# Schematic_Scout2Map_Altium.net
KiCad netlist of a schematic drawn in Altium Designer
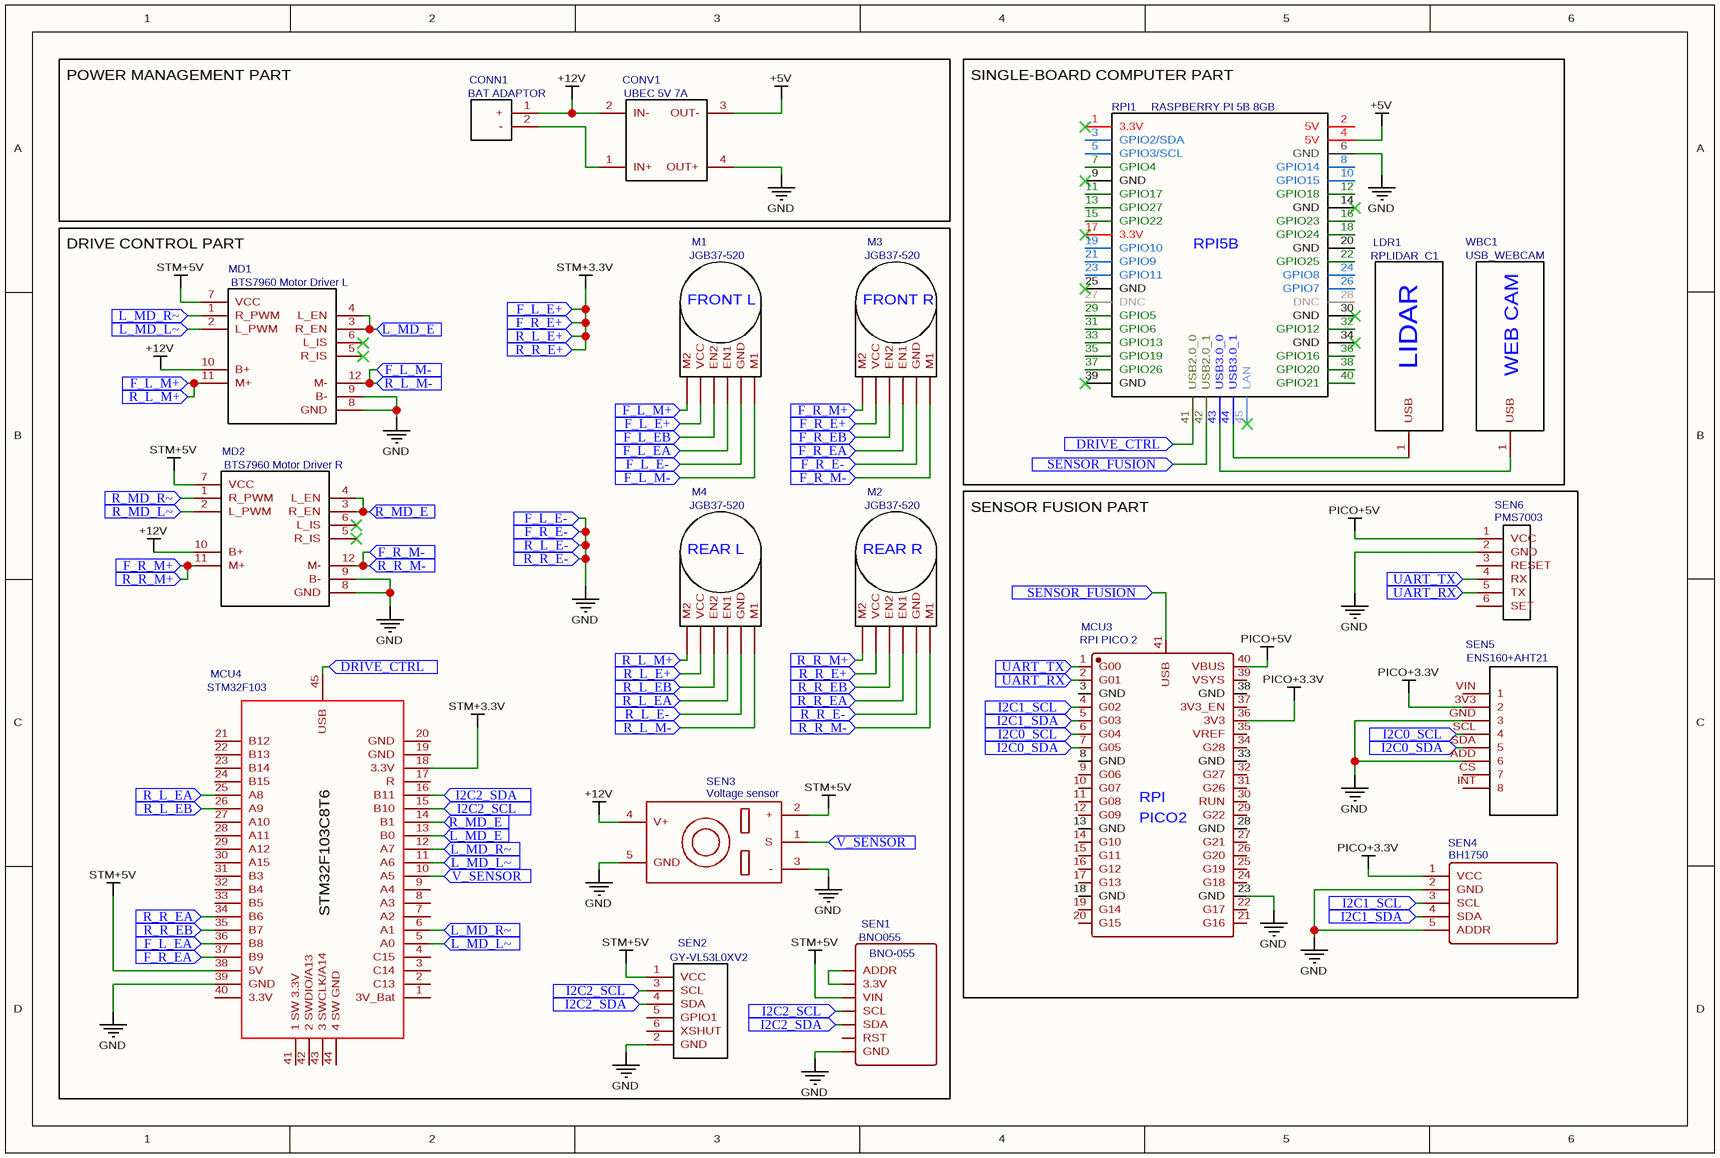
[diagram p0: Schematic_Scout2Map_Altium.schdoc]

(export (version "E")
  (design (tool "Eeschema 10.0.6"))
  (components
    (comp (ref "CONN1")
      (value "BAT ADAPTOR")
      (fields (field (name "CONTRIBUTOR") "odahmohammad361"))
      (libsource (lib "altium-import") (part "root_0_BAT ADAPTOR_"))
    )
    (comp (ref "CONV1")
      (value "UBEC 5V 7A")
      (fields (field (name "CONTRIBUTOR") "Nattanan"))
      (libsource (lib "altium-import") (part "root_1_UBEC 5V 7A_"))
    )
    (comp (ref "LDR1")
      (value "RPLIDAR_C1")
      (fields (field (name "CONTRIBUTOR") "jihoonkimtech (Jihoon Kim)"))
      (libsource (lib "altium-import") (part "root_1_RPLIDAR_C1_"))
    )
    (comp (ref "M1")
      (value "JGB37-520")
      (fields (field (name "CONTRIBUTOR") "preetpatel.svmr"))
      (libsource (lib "altium-import") (part "root_0_JGB37-520_"))
    )
    (comp (ref "M2")
      (value "JGB37-520")
      (fields (field (name "CONTRIBUTOR") "preetpatel.svmr"))
      (libsource (lib "altium-import") (part "root_0_JGB37-520_"))
    )
    (comp (ref "M3")
      (value "JGB37-520")
      (fields (field (name "CONTRIBUTOR") "preetpatel.svmr"))
      (libsource (lib "altium-import") (part "root_0_JGB37-520_"))
    )
    (comp (ref "M4")
      (value "JGB37-520")
      (fields (field (name "CONTRIBUTOR") "preetpatel.svmr"))
      (libsource (lib "altium-import") (part "root_0_JGB37-520_"))
    )
    (comp (ref "MCU3")
      (value "RPI PICO 2")
      (fields
        (field (name "MANUFACTURER") "Raspberry Pi")
        (field (name "MANUFACTURER PART") "SC0918")
        (field (name "CONTRIBUTOR") "jihoonkimtech (Jihoon Kim)")
      )
      (libsource (lib "altium-import") (part "root_0_RPI PICO 2_"))
    )
    (comp (ref "MCU4")
      (value "STM32F103")
      (fields
        (field (name "MANUFACTURER PART") "STM32F103C8T6")
        (field (name "CONTRIBUTOR") "jihoonkimtech (Jihoon Kim)")
      )
      (libsource (lib "altium-import") (part "root_0_STM32F103_"))
    )
    (comp (ref "MD1")
      (value "BTS7960 Motor Driver L")
      (fields (field (name "CONTRIBUTOR") "jihoonkimtech (Jihoon Kim)"))
      (libsource (lib "altium-import") (part "root_0_BTS7960 Motor Driver L_"))
    )
    (comp (ref "MD2")
      (value "BTS7960 Motor Driver R")
      (fields (field (name "CONTRIBUTOR") "jihoonkimtech (Jihoon Kim)"))
      (libsource (lib "altium-import") (part "root_0_BTS7960 Motor Driver R_"))
    )
    (comp (ref "RPI1")
      (value "RASPBERRY PI 5B 8GB")
      (fields
        (field (name "MANUFACTURER") "Raspberry Pi")
        (field (name "MANUFACTURER PART") "Raspberry Pi 4 Model B")
        (field (name "CONTRIBUTOR") "jihoonkimtech (Jihoon Kim)")
      )
      (libsource (lib "altium-import") (part "root_0_RASPBERRY PI 5B 8GB_"))
    )
    (comp (ref "SEN1")
      (value "BNO055")
      (fields (field (name "CONTRIBUTOR") "jihoonkim.tech"))
      (libsource (lib "altium-import") (part "root_0_BNO055_"))
    )
    (comp (ref "SEN2")
      (value "GY-VL53L0XV2")
      (fields (field (name "CONTRIBUTOR") "jihoonkimtech (Jihoon Kim)"))
      (libsource (lib "altium-import") (part "root_0_GY-VL53L0XV2_"))
    )
    (comp (ref "SEN3")
      (value "Voltage sensor")
      (fields (field (name "CONTRIBUTOR") "jihoonkimtech (Jihoon Kim)"))
      (libsource (lib "altium-import") (part "root_0_Voltage sensor_"))
    )
    (comp (ref "SEN4")
      (value "BH1750")
      (fields (field (name "CONTRIBUTOR") "vinhdoan"))
      (libsource (lib "altium-import") (part "root_3_BH1750_"))
    )
    (comp (ref "SEN5")
      (value "ENS160+AHT21")
      (fields (field (name "CONTRIBUTOR") "yoduc"))
      (libsource (lib "altium-import") (part "root_2_ENS160+AHT21_"))
    )
    (comp (ref "SEN6")
      (value "PMS7003")
      (fields (field (name "CONTRIBUTOR") "pb158"))
      (libsource (lib "altium-import") (part "root_0_PMS7003_"))
    )
    (comp (ref "WBC1")
      (value "USB_WEBCAM")
      (fields (field (name "CONTRIBUTOR") "jihoonkimtech (Jihoon Kim)"))
      (libsource (lib "altium-import") (part "root_1_USB_WEBCAM_"))
    )
  )
  (nets
    (net (code "1") (name "+5V") (class "Default")
      (node (ref "CONV1") (pin "3") (pinfunction "OUT-_3") (pintype "passive"))
      (node (ref "RPI1") (pin "4") (pinfunction "5V_4") (pintype "passive"))
    )
    (net (code "2") (name "+12V") (class "Default")
      (node (ref "CONN1") (pin "1") (pinfunction "+_1") (pintype "passive"))
      (node (ref "CONV1") (pin "2") (pinfunction "IN-_2") (pintype "passive"))
      (node (ref "MD1") (pin "10") (pinfunction "B+_10") (pintype "passive"))
      (node (ref "MD2") (pin "10") (pinfunction "B+_10") (pintype "passive"))
      (node (ref "SEN3") (pin "4") (pinfunction "V+_4") (pintype "passive"))
    )
    (net (code "3") (name "/DRIVE_CTRL") (class "Default")
      (node (ref "MCU4") (pin "45") (pinfunction "USB_45") (pintype "passive"))
      (node (ref "RPI1") (pin "41") (pinfunction "USB2.0_0_41") (pintype "passive"))
    )
    (net (code "4") (name "/F_L_EA") (class "Default")
      (node (ref "M1") (pin "3") (pinfunction "EN1_3") (pintype "passive"))
      (node (ref "MCU4") (pin "36") (pinfunction "B8_36") (pintype "passive"))
    )
    (net (code "5") (name "/F_L_EB") (class "Default")
      (node (ref "M1") (pin "4") (pinfunction "EN2_4") (pintype "passive"))
    )
    (net (code "6") (name "/F_L_M+") (class "Default")
      (node (ref "M1") (pin "6") (pinfunction "M2_6") (pintype "passive"))
      (node (ref "M4") (pin "6") (pinfunction "M2_6") (pintype "passive"))
      (node (ref "MD1") (pin "11") (pinfunction "M+_11") (pintype "passive"))
    )
    (net (code "7") (name "/F_L_M-") (class "Default")
      (node (ref "M1") (pin "1") (pinfunction "M1_1") (pintype "passive"))
      (node (ref "M4") (pin "1") (pinfunction "M1_1") (pintype "passive"))
      (node (ref "MD1") (pin "12") (pinfunction "M-_12") (pintype "passive"))
    )
    (net (code "8") (name "/F_R_EA") (class "Default")
      (node (ref "M3") (pin "3") (pinfunction "EN1_3") (pintype "passive"))
      (node (ref "MCU4") (pin "37") (pinfunction "B9_37") (pintype "passive"))
    )
    (net (code "9") (name "/F_R_EB") (class "Default")
      (node (ref "M3") (pin "4") (pinfunction "EN2_4") (pintype "passive"))
    )
    (net (code "10") (name "/F_R_M+") (class "Default")
      (node (ref "M2") (pin "6") (pinfunction "M2_6") (pintype "passive"))
      (node (ref "M3") (pin "6") (pinfunction "M2_6") (pintype "passive"))
      (node (ref "MD2") (pin "11") (pinfunction "M+_11") (pintype "passive"))
    )
    (net (code "11") (name "/F_R_M-") (class "Default")
      (node (ref "M2") (pin "1") (pinfunction "M1_1") (pintype "passive"))
      (node (ref "M3") (pin "1") (pinfunction "M1_1") (pintype "passive"))
      (node (ref "MD2") (pin "12") (pinfunction "M-_12") (pintype "passive"))
    )
    (net (code "12") (name "/I2C0_SCL") (class "Default")
      (node (ref "MCU3") (pin "6") (pinfunction "G04_6") (pintype "passive"))
      (node (ref "SEN5") (pin "SCL") (pinfunction "4_SCL") (pintype "passive"))
    )
    (net (code "13") (name "/I2C0_SDA") (class "Default")
      (node (ref "MCU3") (pin "7") (pinfunction "G05_7") (pintype "passive"))
      (node (ref "SEN5") (pin "SDA") (pinfunction "5_SDA") (pintype "passive"))
    )
    (net (code "14") (name "/I2C1_SCL") (class "Default")
      (node (ref "MCU3") (pin "4") (pinfunction "G02_4") (pintype "passive"))
      (node (ref "SEN4") (pin "3") (pinfunction "SCL_3") (pintype "passive"))
    )
    (net (code "15") (name "/I2C1_SDA") (class "Default")
      (node (ref "MCU3") (pin "5") (pinfunction "G03_5") (pintype "passive"))
      (node (ref "SEN4") (pin "4") (pinfunction "SDA_4") (pintype "passive"))
    )
    (net (code "16") (name "/I2C2_SCL") (class "Default")
      (node (ref "MCU4") (pin "15") (pinfunction "B10_15") (pintype "passive"))
      (node (ref "SEN1") (pin "4") (pinfunction "SCL_4") (pintype "passive"))
      (node (ref "SEN2") (pin "3") (pinfunction "SCL_3") (pintype "passive"))
    )
    (net (code "17") (name "/I2C2_SDA") (class "Default")
      (node (ref "MCU4") (pin "16") (pinfunction "B11_16") (pintype "passive"))
      (node (ref "SEN1") (pin "5") (pinfunction "SDA_5") (pintype "passive"))
      (node (ref "SEN2") (pin "4") (pinfunction "SDA_4") (pintype "passive"))
    )
    (net (code "18") (name "/L_MD_E") (class "Default")
      (node (ref "MCU4") (pin "13") (pinfunction "B0_13") (pintype "passive"))
      (node (ref "MD1") (pin "3") (pinfunction "R_EN_3") (pintype "passive"))
      (node (ref "MD1") (pin "4") (pinfunction "L_EN_4") (pintype "passive"))
    )
    (net (code "19") (name "/L_MD_L~") (class "Default")
      (node (ref "MCU4") (pin "11") (pinfunction "A6_11") (pintype "passive"))
      (node (ref "MCU4") (pin "5") (pinfunction "A0_5") (pintype "passive"))
      (node (ref "MD1") (pin "2") (pinfunction "L_PWM_2") (pintype "passive"))
    )
    (net (code "20") (name "/L_MD_R~") (class "Default")
      (node (ref "MCU4") (pin "12") (pinfunction "A7_12") (pintype "passive"))
      (node (ref "MCU4") (pin "6") (pinfunction "A1_6") (pintype "passive"))
      (node (ref "MD1") (pin "1") (pinfunction "R_PWM_1") (pintype "passive"))
    )
    (net (code "21") (name "/R_L_EA") (class "Default")
      (node (ref "M4") (pin "3") (pinfunction "EN1_3") (pintype "passive"))
      (node (ref "MCU4") (pin "25") (pinfunction "A8_25") (pintype "passive"))
    )
    (net (code "22") (name "/R_L_EB") (class "Default")
      (node (ref "M4") (pin "4") (pinfunction "EN2_4") (pintype "passive"))
      (node (ref "MCU4") (pin "26") (pinfunction "A9_26") (pintype "passive"))
    )
    (net (code "23") (name "/R_MD_E") (class "Default")
      (node (ref "MCU4") (pin "14") (pinfunction "B1_14") (pintype "passive"))
      (node (ref "MD2") (pin "3") (pinfunction "R_EN_3") (pintype "passive"))
      (node (ref "MD2") (pin "4") (pinfunction "L_EN_4") (pintype "passive"))
    )
    (net (code "24") (name "/R_MD_L~") (class "Default")
      (node (ref "MD2") (pin "2") (pinfunction "L_PWM_2") (pintype "passive"))
    )
    (net (code "25") (name "/R_MD_R~") (class "Default")
      (node (ref "MD2") (pin "1") (pinfunction "R_PWM_1") (pintype "passive"))
    )
    (net (code "26") (name "/R_R_EA") (class "Default")
      (node (ref "M2") (pin "3") (pinfunction "EN1_3") (pintype "passive"))
      (node (ref "MCU4") (pin "34") (pinfunction "B6_34") (pintype "passive"))
    )
    (net (code "27") (name "/R_R_EB") (class "Default")
      (node (ref "M2") (pin "4") (pinfunction "EN2_4") (pintype "passive"))
      (node (ref "MCU4") (pin "35") (pinfunction "B7_35") (pintype "passive"))
    )
    (net (code "28") (name "/SENSOR_FUSION") (class "Default")
      (node (ref "MCU3") (pin "41") (pinfunction "USB_41") (pintype "passive"))
      (node (ref "RPI1") (pin "42") (pinfunction "USB2.0_1_42") (pintype "passive"))
    )
    (net (code "29") (name "/UART_RX") (class "Default")
      (node (ref "MCU3") (pin "2") (pinfunction "G01_2") (pintype "passive"))
      (node (ref "SEN6") (pin "5") (pinfunction "TX_5") (pintype "passive"))
    )
    (net (code "30") (name "/UART_TX") (class "Default")
      (node (ref "MCU3") (pin "1") (pinfunction "G00_1") (pintype "passive"))
      (node (ref "SEN6") (pin "4") (pinfunction "RX_4") (pintype "passive"))
    )
    (net (code "31") (name "/V_SENSOR") (class "Default")
      (node (ref "MCU4") (pin "10") (pinfunction "A5_10") (pintype "passive"))
      (node (ref "SEN3") (pin "1") (pinfunction "S_1") (pintype "passive"))
    )
    (net (code "32") (name "GND") (class "Default")
      (node (ref "CONV1") (pin "4") (pinfunction "OUT+_4") (pintype "passive"))
      (node (ref "M1") (pin "2") (pinfunction "GND_2") (pintype "passive"))
      (node (ref "M2") (pin "2") (pinfunction "GND_2") (pintype "passive"))
      (node (ref "M3") (pin "2") (pinfunction "GND_2") (pintype "passive"))
      (node (ref "M4") (pin "2") (pinfunction "GND_2") (pintype "passive"))
      (node (ref "MCU3") (pin "23") (pinfunction "GND_23") (pintype "passive"))
      (node (ref "MCU4") (pin "39") (pinfunction "GND_39") (pintype "passive"))
      (node (ref "MD1") (pin "8") (pinfunction "GND_8") (pintype "passive"))
      (node (ref "MD1") (pin "9") (pinfunction "B-_9") (pintype "passive"))
      (node (ref "MD2") (pin "8") (pinfunction "GND_8") (pintype "passive"))
      (node (ref "MD2") (pin "9") (pinfunction "B-_9") (pintype "passive"))
      (node (ref "RPI1") (pin "6") (pinfunction "GND_6") (pintype "passive"))
      (node (ref "SEN1") (pin "3") (pinfunction "GND_3") (pintype "passive"))
      (node (ref "SEN2") (pin "2") (pinfunction "GND_2") (pintype "passive"))
      (node (ref "SEN3") (pin "3") (pinfunction "-_3") (pintype "passive"))
      (node (ref "SEN3") (pin "5") (pinfunction "GND_5") (pintype "passive"))
      (node (ref "SEN4") (pin "2") (pinfunction "GND_2") (pintype "passive"))
      (node (ref "SEN4") (pin "5") (pinfunction "ADDR_5") (pintype "passive"))
      (node (ref "SEN5") (pin "ADD") (pinfunction "6_ADD") (pintype "passive"))
      (node (ref "SEN5") (pin "GND") (pinfunction "3_GND") (pintype "passive"))
      (node (ref "SEN6") (pin "2") (pinfunction "GND_2") (pintype "passive"))
    )
    (net (code "33") (name "Net-(CONN1--)") (class "Default")
      (node (ref "CONN1") (pin "2") (pinfunction "-_2") (pintype "passive"))
      (node (ref "CONV1") (pin "1") (pinfunction "IN+_1") (pintype "passive"))
    )
    (net (code "34") (name "Net-(LDR1-USB)") (class "Default")
      (node (ref "LDR1") (pin "1") (pinfunction "USB_1") (pintype "passive"))
      (node (ref "RPI1") (pin "44") (pinfunction "USB3.0_1_44") (pintype "passive"))
    )
    (net (code "35") (name "Net-(RPI1-USB3.0_0)") (class "Default")
      (node (ref "RPI1") (pin "43") (pinfunction "USB3.0_0_43") (pintype "passive"))
      (node (ref "WBC1") (pin "1") (pinfunction "USB_1") (pintype "passive"))
    )
    (net (code "36") (name "Net-(SEN1-3.3V)") (class "Default")
      (node (ref "SEN1") (pin "2") (pinfunction "3.3V_2") (pintype "passive"))
      (node (ref "SEN1") (pin "6") (pinfunction "ADDR_6") (pintype "passive"))
    )
    (net (code "37") (name "PICO+3.3V") (class "Default")
      (node (ref "MCU3") (pin "36") (pinfunction "3V3_36") (pintype "passive"))
      (node (ref "SEN4") (pin "1") (pinfunction "VCC_1") (pintype "passive"))
      (node (ref "SEN5") (pin "3V3") (pinfunction "2_3V3") (pintype "passive"))
    )
    (net (code "38") (name "PICO+5V") (class "Default")
      (node (ref "MCU3") (pin "40") (pinfunction "VBUS_40") (pintype "passive"))
      (node (ref "SEN6") (pin "1") (pinfunction "VCC_1") (pintype "passive"))
    )
    (net (code "39") (name "STM+3.3V") (class "Default")
      (node (ref "M1") (pin "5") (pinfunction "VCC_5") (pintype "passive"))
      (node (ref "M2") (pin "5") (pinfunction "VCC_5") (pintype "passive"))
      (node (ref "M3") (pin "5") (pinfunction "VCC_5") (pintype "passive"))
      (node (ref "M4") (pin "5") (pinfunction "VCC_5") (pintype "passive"))
      (node (ref "MCU4") (pin "18") (pinfunction "3.3V_18") (pintype "passive"))
    )
    (net (code "40") (name "STM+5V") (class "Default")
      (node (ref "MCU4") (pin "38") (pinfunction "5V_38") (pintype "passive"))
      (node (ref "MD1") (pin "7") (pinfunction "VCC_7") (pintype "passive"))
      (node (ref "MD2") (pin "7") (pinfunction "VCC_7") (pintype "passive"))
      (node (ref "SEN1") (pin "1") (pinfunction "VIN_1") (pintype "passive"))
      (node (ref "SEN2") (pin "1") (pinfunction "VCC_1") (pintype "passive"))
      (node (ref "SEN3") (pin "2") (pinfunction "+_2") (pintype "passive"))
    )
    (net (code "41") (name "unconnected-(MCU3-3V3_EN-Pad37)") (class "Default")
      (node (ref "MCU3") (pin "37") (pinfunction "3V3_EN_37") (pintype "passive"))
    )
    (net (code "42") (name "unconnected-(MCU3-G06-Pad9)") (class "Default")
      (node (ref "MCU3") (pin "9") (pinfunction "G06_9") (pintype "passive"))
    )
    (net (code "43") (name "unconnected-(MCU3-G07-Pad10)") (class "Default")
      (node (ref "MCU3") (pin "10") (pinfunction "G07_10") (pintype "passive"))
    )
    (net (code "44") (name "unconnected-(MCU3-G08-Pad11)") (class "Default")
      (node (ref "MCU3") (pin "11") (pinfunction "G08_11") (pintype "passive"))
    )
    (net (code "45") (name "unconnected-(MCU3-G09-Pad12)") (class "Default")
      (node (ref "MCU3") (pin "12") (pinfunction "G09_12") (pintype "passive"))
    )
    (net (code "46") (name "unconnected-(MCU3-G10-Pad14)") (class "Default")
      (node (ref "MCU3") (pin "14") (pinfunction "G10_14") (pintype "passive"))
    )
    (net (code "47") (name "unconnected-(MCU3-G11-Pad15)") (class "Default")
      (node (ref "MCU3") (pin "15") (pinfunction "G11_15") (pintype "passive"))
    )
    (net (code "48") (name "unconnected-(MCU3-G12-Pad16)") (class "Default")
      (node (ref "MCU3") (pin "16") (pinfunction "G12_16") (pintype "passive"))
    )
    (net (code "49") (name "unconnected-(MCU3-G13-Pad17)") (class "Default")
      (node (ref "MCU3") (pin "17") (pinfunction "G13_17") (pintype "passive"))
    )
    (net (code "50") (name "unconnected-(MCU3-G14-Pad19)") (class "Default")
      (node (ref "MCU3") (pin "19") (pinfunction "G14_19") (pintype "passive"))
    )
    (net (code "51") (name "unconnected-(MCU3-G15-Pad20)") (class "Default")
      (node (ref "MCU3") (pin "20") (pinfunction "G15_20") (pintype "passive"))
    )
    (net (code "52") (name "unconnected-(MCU3-G16-Pad21)") (class "Default")
      (node (ref "MCU3") (pin "21") (pinfunction "G16_21") (pintype "passive"))
    )
    (net (code "53") (name "unconnected-(MCU3-G17-Pad22)") (class "Default")
      (node (ref "MCU3") (pin "22") (pinfunction "G17_22") (pintype "passive"))
    )
    (net (code "54") (name "unconnected-(MCU3-G18-Pad24)") (class "Default")
      (node (ref "MCU3") (pin "24") (pinfunction "G18_24") (pintype "passive"))
    )
    (net (code "55") (name "unconnected-(MCU3-G19-Pad25)") (class "Default")
      (node (ref "MCU3") (pin "25") (pinfunction "G19_25") (pintype "passive"))
    )
    (net (code "56") (name "unconnected-(MCU3-G20-Pad26)") (class "Default")
      (node (ref "MCU3") (pin "26") (pinfunction "G20_26") (pintype "passive"))
    )
    (net (code "57") (name "unconnected-(MCU3-G21-Pad27)") (class "Default")
      (node (ref "MCU3") (pin "27") (pinfunction "G21_27") (pintype "passive"))
    )
    (net (code "58") (name "unconnected-(MCU3-G22-Pad29)") (class "Default")
      (node (ref "MCU3") (pin "29") (pinfunction "G22_29") (pintype "passive"))
    )
    (net (code "59") (name "unconnected-(MCU3-G26-Pad31)") (class "Default")
      (node (ref "MCU3") (pin "31") (pinfunction "G26_31") (pintype "passive"))
    )
    (net (code "60") (name "unconnected-(MCU3-G27-Pad32)") (class "Default")
      (node (ref "MCU3") (pin "32") (pinfunction "G27_32") (pintype "passive"))
    )
    (net (code "61") (name "unconnected-(MCU3-G28-Pad34)") (class "Default")
      (node (ref "MCU3") (pin "34") (pinfunction "G28_34") (pintype "passive"))
    )
    (net (code "62") (name "unconnected-(MCU3-GND-Pad3)") (class "Default")
      (node (ref "MCU3") (pin "3") (pinfunction "GND_3") (pintype "passive"))
    )
    (net (code "63") (name "unconnected-(MCU3-GND-Pad8)") (class "Default")
      (node (ref "MCU3") (pin "8") (pinfunction "GND_8") (pintype "passive"))
    )
    (net (code "64") (name "unconnected-(MCU3-GND-Pad13)") (class "Default")
      (node (ref "MCU3") (pin "13") (pinfunction "GND_13") (pintype "passive"))
    )
    (net (code "65") (name "unconnected-(MCU3-GND-Pad18)") (class "Default")
      (node (ref "MCU3") (pin "18") (pinfunction "GND_18") (pintype "passive"))
    )
    (net (code "66") (name "unconnected-(MCU3-GND-Pad28)") (class "Default")
      (node (ref "MCU3") (pin "28") (pinfunction "GND_28") (pintype "passive"))
    )
    (net (code "67") (name "unconnected-(MCU3-GND-Pad33)") (class "Default")
      (node (ref "MCU3") (pin "33") (pinfunction "GND_33") (pintype "passive"))
    )
    (net (code "68") (name "unconnected-(MCU3-GND-Pad38)") (class "Default")
      (node (ref "MCU3") (pin "38") (pinfunction "GND_38") (pintype "passive"))
    )
    (net (code "69") (name "unconnected-(MCU3-RUN-Pad30)") (class "Default")
      (node (ref "MCU3") (pin "30") (pinfunction "RUN_30") (pintype "passive"))
    )
    (net (code "70") (name "unconnected-(MCU3-VREF-Pad35)") (class "Default")
      (node (ref "MCU3") (pin "35") (pinfunction "VREF_35") (pintype "passive"))
    )
    (net (code "71") (name "unconnected-(MCU3-VSYS-Pad39)") (class "Default")
      (node (ref "MCU3") (pin "39") (pinfunction "VSYS_39") (pintype "passive"))
    )
    (net (code "72") (name "unconnected-(MCU4-1_SW_3.3V-Pad41)") (class "Default")
      (node (ref "MCU4") (pin "41") (pinfunction "1_SW_3.3V_41") (pintype "passive"))
    )
    (net (code "73") (name "unconnected-(MCU4-2_SWDIO{slash}A13-Pad42)") (class "Default")
      (node (ref "MCU4") (pin "42") (pinfunction "2_SWDIO/A13_42") (pintype "passive"))
    )
    (net (code "74") (name "unconnected-(MCU4-3.3V-Pad40)") (class "Default")
      (node (ref "MCU4") (pin "40") (pinfunction "3.3V_40") (pintype "passive"))
    )
    (net (code "75") (name "unconnected-(MCU4-3V_Bat-Pad1)") (class "Default")
      (node (ref "MCU4") (pin "1") (pinfunction "3V_Bat_1") (pintype "passive"))
    )
    (net (code "76") (name "unconnected-(MCU4-3_SWCLK{slash}A14-Pad43)") (class "Default")
      (node (ref "MCU4") (pin "43") (pinfunction "3_SWCLK/A14_43") (pintype "passive"))
    )
    (net (code "77") (name "unconnected-(MCU4-4_SW_GND-Pad44)") (class "Default")
      (node (ref "MCU4") (pin "44") (pinfunction "4_SW_GND_44") (pintype "passive"))
    )
    (net (code "78") (name "unconnected-(MCU4-A2-Pad7)") (class "Default")
      (node (ref "MCU4") (pin "7") (pinfunction "A2_7") (pintype "passive"))
    )
    (net (code "79") (name "unconnected-(MCU4-A3-Pad8)") (class "Default")
      (node (ref "MCU4") (pin "8") (pinfunction "A3_8") (pintype "passive"))
    )
    (net (code "80") (name "unconnected-(MCU4-A4-Pad9)") (class "Default")
      (node (ref "MCU4") (pin "9") (pinfunction "A4_9") (pintype "passive"))
    )
    (net (code "81") (name "unconnected-(MCU4-A10-Pad27)") (class "Default")
      (node (ref "MCU4") (pin "27") (pinfunction "A10_27") (pintype "passive"))
    )
    (net (code "82") (name "unconnected-(MCU4-A11-Pad28)") (class "Default")
      (node (ref "MCU4") (pin "28") (pinfunction "A11_28") (pintype "passive"))
    )
    (net (code "83") (name "unconnected-(MCU4-A12-Pad29)") (class "Default")
      (node (ref "MCU4") (pin "29") (pinfunction "A12_29") (pintype "passive"))
    )
    (net (code "84") (name "unconnected-(MCU4-A15-Pad30)") (class "Default")
      (node (ref "MCU4") (pin "30") (pinfunction "A15_30") (pintype "passive"))
    )
    (net (code "85") (name "unconnected-(MCU4-B3-Pad31)") (class "Default")
      (node (ref "MCU4") (pin "31") (pinfunction "B3_31") (pintype "passive"))
    )
    (net (code "86") (name "unconnected-(MCU4-B4-Pad32)") (class "Default")
      (node (ref "MCU4") (pin "32") (pinfunction "B4_32") (pintype "passive"))
    )
    (net (code "87") (name "unconnected-(MCU4-B5-Pad33)") (class "Default")
      (node (ref "MCU4") (pin "33") (pinfunction "B5_33") (pintype "passive"))
    )
    (net (code "88") (name "unconnected-(MCU4-B12-Pad21)") (class "Default")
      (node (ref "MCU4") (pin "21") (pinfunction "B12_21") (pintype "passive"))
    )
    (net (code "89") (name "unconnected-(MCU4-B13-Pad22)") (class "Default")
      (node (ref "MCU4") (pin "22") (pinfunction "B13_22") (pintype "passive"))
    )
    (net (code "90") (name "unconnected-(MCU4-B14-Pad23)") (class "Default")
      (node (ref "MCU4") (pin "23") (pinfunction "B14_23") (pintype "passive"))
    )
    (net (code "91") (name "unconnected-(MCU4-B15-Pad24)") (class "Default")
      (node (ref "MCU4") (pin "24") (pinfunction "B15_24") (pintype "passive"))
    )
    (net (code "92") (name "unconnected-(MCU4-C13-Pad2)") (class "Default")
      (node (ref "MCU4") (pin "2") (pinfunction "C13_2") (pintype "passive"))
    )
    (net (code "93") (name "unconnected-(MCU4-C14-Pad3)") (class "Default")
      (node (ref "MCU4") (pin "3") (pinfunction "C14_3") (pintype "passive"))
    )
    (net (code "94") (name "unconnected-(MCU4-C15-Pad4)") (class "Default")
      (node (ref "MCU4") (pin "4") (pinfunction "C15_4") (pintype "passive"))
    )
    (net (code "95") (name "unconnected-(MCU4-GND-Pad19)") (class "Default")
      (node (ref "MCU4") (pin "19") (pinfunction "GND_19") (pintype "passive"))
    )
    (net (code "96") (name "unconnected-(MCU4-GND-Pad20)") (class "Default")
      (node (ref "MCU4") (pin "20") (pinfunction "GND_20") (pintype "passive"))
    )
    (net (code "97") (name "unconnected-(MCU4-R-Pad17)") (class "Default")
      (node (ref "MCU4") (pin "17") (pinfunction "R_17") (pintype "passive"))
    )
    (net (code "98") (name "unconnected-(MD1-L_IS-Pad6)") (class "Default")
      (node (ref "MD1") (pin "6") (pinfunction "L_IS_6") (pintype "passive+no_connect"))
    )
    (net (code "99") (name "unconnected-(MD1-R_IS-Pad5)") (class "Default")
      (node (ref "MD1") (pin "5") (pinfunction "R_IS_5") (pintype "passive+no_connect"))
    )
    (net (code "100") (name "unconnected-(MD2-L_IS-Pad6)") (class "Default")
      (node (ref "MD2") (pin "6") (pinfunction "L_IS_6") (pintype "passive+no_connect"))
    )
    (net (code "101") (name "unconnected-(MD2-R_IS-Pad5)") (class "Default")
      (node (ref "MD2") (pin "5") (pinfunction "R_IS_5") (pintype "passive+no_connect"))
    )
    (net (code "102") (name "unconnected-(RPI1-3.3V-Pad1)") (class "Default")
      (node (ref "RPI1") (pin "1") (pinfunction "3.3V_1") (pintype "passive+no_connect"))
    )
    (net (code "103") (name "unconnected-(RPI1-3.3V-Pad17)") (class "Default")
      (node (ref "RPI1") (pin "17") (pinfunction "3.3V_17") (pintype "passive+no_connect"))
    )
    (net (code "104") (name "unconnected-(RPI1-5V-Pad2)") (class "Default")
      (node (ref "RPI1") (pin "2") (pinfunction "5V_2") (pintype "passive"))
    )
    (net (code "105") (name "unconnected-(RPI1-DNC-Pad27)") (class "Default")
      (node (ref "RPI1") (pin "27") (pinfunction "DNC_27") (pintype "passive"))
    )
    (net (code "106") (name "unconnected-(RPI1-DNC-Pad28)") (class "Default")
      (node (ref "RPI1") (pin "28") (pinfunction "DNC_28") (pintype "passive"))
    )
    (net (code "107") (name "unconnected-(RPI1-GND-Pad9)") (class "Default")
      (node (ref "RPI1") (pin "9") (pinfunction "GND_9") (pintype "passive+no_connect"))
    )
    (net (code "108") (name "unconnected-(RPI1-GND-Pad14)") (class "Default")
      (node (ref "RPI1") (pin "14") (pinfunction "GND_14") (pintype "passive+no_connect"))
    )
    (net (code "109") (name "unconnected-(RPI1-GND-Pad20)") (class "Default")
      (node (ref "RPI1") (pin "20") (pinfunction "GND_20") (pintype "passive"))
    )
    (net (code "110") (name "unconnected-(RPI1-GND-Pad25)") (class "Default")
      (node (ref "RPI1") (pin "25") (pinfunction "GND_25") (pintype "passive+no_connect"))
    )
    (net (code "111") (name "unconnected-(RPI1-GND-Pad30)") (class "Default")
      (node (ref "RPI1") (pin "30") (pinfunction "GND_30") (pintype "passive+no_connect"))
    )
    (net (code "112") (name "unconnected-(RPI1-GND-Pad34)") (class "Default")
      (node (ref "RPI1") (pin "34") (pinfunction "GND_34") (pintype "passive+no_connect"))
    )
    (net (code "113") (name "unconnected-(RPI1-GND-Pad39)") (class "Default")
      (node (ref "RPI1") (pin "39") (pinfunction "GND_39") (pintype "passive+no_connect"))
    )
    (net (code "114") (name "unconnected-(RPI1-GPIO2{slash}SDA-Pad3)") (class "Default")
      (node (ref "RPI1") (pin "3") (pinfunction "GPIO2/SDA_3") (pintype "passive"))
    )
    (net (code "115") (name "unconnected-(RPI1-GPIO3{slash}SCL-Pad5)") (class "Default")
      (node (ref "RPI1") (pin "5") (pinfunction "GPIO3/SCL_5") (pintype "passive"))
    )
    (net (code "116") (name "unconnected-(RPI1-GPIO4-Pad7)") (class "Default")
      (node (ref "RPI1") (pin "7") (pinfunction "GPIO4_7") (pintype "passive"))
    )
    (net (code "117") (name "unconnected-(RPI1-GPIO5-Pad29)") (class "Default")
      (node (ref "RPI1") (pin "29") (pinfunction "GPIO5_29") (pintype "passive"))
    )
    (net (code "118") (name "unconnected-(RPI1-GPIO6-Pad31)") (class "Default")
      (node (ref "RPI1") (pin "31") (pinfunction "GPIO6_31") (pintype "passive"))
    )
    (net (code "119") (name "unconnected-(RPI1-GPIO7-Pad26)") (class "Default")
      (node (ref "RPI1") (pin "26") (pinfunction "GPIO7_26") (pintype "passive"))
    )
    (net (code "120") (name "unconnected-(RPI1-GPIO8-Pad24)") (class "Default")
      (node (ref "RPI1") (pin "24") (pinfunction "GPIO8_24") (pintype "passive"))
    )
    (net (code "121") (name "unconnected-(RPI1-GPIO9-Pad21)") (class "Default")
      (node (ref "RPI1") (pin "21") (pinfunction "GPIO9_21") (pintype "passive"))
    )
    (net (code "122") (name "unconnected-(RPI1-GPIO10-Pad19)") (class "Default")
      (node (ref "RPI1") (pin "19") (pinfunction "GPIO10_19") (pintype "passive"))
    )
    (net (code "123") (name "unconnected-(RPI1-GPIO11-Pad23)") (class "Default")
      (node (ref "RPI1") (pin "23") (pinfunction "GPIO11_23") (pintype "passive"))
    )
    (net (code "124") (name "unconnected-(RPI1-GPIO12-Pad32)") (class "Default")
      (node (ref "RPI1") (pin "32") (pinfunction "GPIO12_32") (pintype "passive"))
    )
    (net (code "125") (name "unconnected-(RPI1-GPIO13-Pad33)") (class "Default")
      (node (ref "RPI1") (pin "33") (pinfunction "GPIO13_33") (pintype "passive"))
    )
    (net (code "126") (name "unconnected-(RPI1-GPIO14-Pad8)") (class "Default")
      (node (ref "RPI1") (pin "8") (pinfunction "GPIO14_8") (pintype "passive"))
    )
    (net (code "127") (name "unconnected-(RPI1-GPIO15-Pad10)") (class "Default")
      (node (ref "RPI1") (pin "10") (pinfunction "GPIO15_10") (pintype "passive"))
    )
    (net (code "128") (name "unconnected-(RPI1-GPIO16-Pad36)") (class "Default")
      (node (ref "RPI1") (pin "36") (pinfunction "GPIO16_36") (pintype "passive"))
    )
    (net (code "129") (name "unconnected-(RPI1-GPIO17-Pad11)") (class "Default")
      (node (ref "RPI1") (pin "11") (pinfunction "GPIO17_11") (pintype "passive"))
    )
    (net (code "130") (name "unconnected-(RPI1-GPIO18-Pad12)") (class "Default")
      (node (ref "RPI1") (pin "12") (pinfunction "GPIO18_12") (pintype "passive"))
    )
    (net (code "131") (name "unconnected-(RPI1-GPIO19-Pad35)") (class "Default")
      (node (ref "RPI1") (pin "35") (pinfunction "GPIO19_35") (pintype "passive"))
    )
    (net (code "132") (name "unconnected-(RPI1-GPIO20-Pad38)") (class "Default")
      (node (ref "RPI1") (pin "38") (pinfunction "GPIO20_38") (pintype "passive"))
    )
    (net (code "133") (name "unconnected-(RPI1-GPIO21-Pad40)") (class "Default")
      (node (ref "RPI1") (pin "40") (pinfunction "GPIO21_40") (pintype "passive"))
    )
    (net (code "134") (name "unconnected-(RPI1-GPIO22-Pad15)") (class "Default")
      (node (ref "RPI1") (pin "15") (pinfunction "GPIO22_15") (pintype "passive"))
    )
    (net (code "135") (name "unconnected-(RPI1-GPIO23-Pad16)") (class "Default")
      (node (ref "RPI1") (pin "16") (pinfunction "GPIO23_16") (pintype "passive"))
    )
    (net (code "136") (name "unconnected-(RPI1-GPIO24-Pad18)") (class "Default")
      (node (ref "RPI1") (pin "18") (pinfunction "GPIO24_18") (pintype "passive"))
    )
    (net (code "137") (name "unconnected-(RPI1-GPIO25-Pad22)") (class "Default")
      (node (ref "RPI1") (pin "22") (pinfunction "GPIO25_22") (pintype "passive"))
    )
    (net (code "138") (name "unconnected-(RPI1-GPIO26-Pad37)") (class "Default")
      (node (ref "RPI1") (pin "37") (pinfunction "GPIO26_37") (pintype "passive"))
    )
    (net (code "139") (name "unconnected-(RPI1-GPIO27-Pad13)") (class "Default")
      (node (ref "RPI1") (pin "13") (pinfunction "GPIO27_13") (pintype "passive"))
    )
    (net (code "140") (name "unconnected-(RPI1-LAN-Pad45)") (class "Default")
      (node (ref "RPI1") (pin "45") (pinfunction "LAN_45") (pintype "passive+no_connect"))
    )
    (net (code "141") (name "unconnected-(SEN1-RST-Pad7)") (class "Default")
      (node (ref "SEN1") (pin "7") (pinfunction "RST_7") (pintype "passive"))
    )
    (net (code "142") (name "unconnected-(SEN2-GPIO1-Pad5)") (class "Default")
      (node (ref "SEN2") (pin "5") (pinfunction "GPIO1_5") (pintype "passive"))
    )
    (net (code "143") (name "unconnected-(SEN2-XSHUT-Pad6)") (class "Default")
      (node (ref "SEN2") (pin "6") (pinfunction "XSHUT_6") (pintype "passive"))
    )
    (net (code "144") (name "unconnected-(SEN5-1-PadVIN)") (class "Default")
      (node (ref "SEN5") (pin "VIN") (pinfunction "1_VIN") (pintype "passive"))
    )
    (net (code "145") (name "unconnected-(SEN5-7-PadCS)") (class "Default")
      (node (ref "SEN5") (pin "CS") (pinfunction "7_CS") (pintype "passive"))
    )
    (net (code "146") (name "unconnected-(SEN5-8-PadINT)") (class "Default")
      (node (ref "SEN5") (pin "INT") (pinfunction "8_INT") (pintype "passive"))
    )
    (net (code "147") (name "unconnected-(SEN6-RESET-Pad3)") (class "Default")
      (node (ref "SEN6") (pin "3") (pinfunction "RESET_3") (pintype "passive"))
    )
    (net (code "148") (name "unconnected-(SEN6-SET-Pad6)") (class "Default")
      (node (ref "SEN6") (pin "6") (pinfunction "SET_6") (pintype "passive"))
    )
  )
)
